# Tea_Cabinet.net
KiCad netlist of a schematic drawn in EAGLE
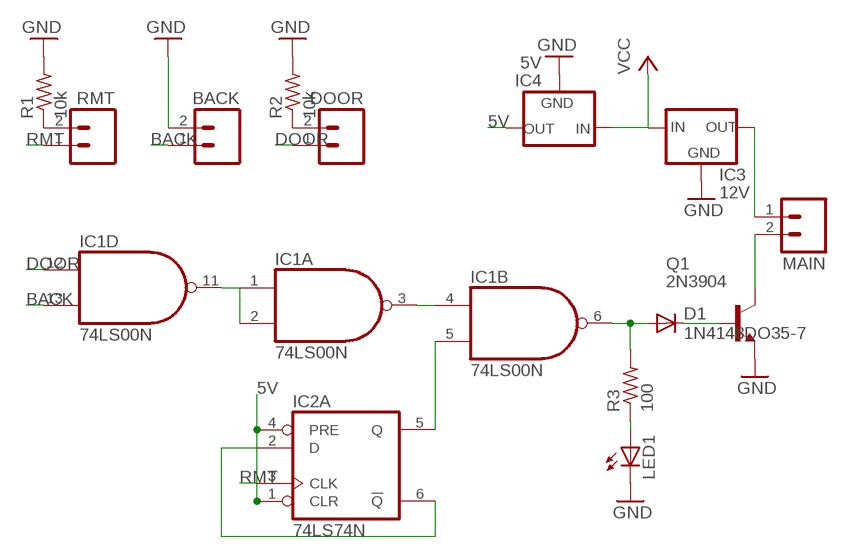
[diagram p0: schematic, sheet 1]

(export (version "E")
  (design (tool "Eeschema 10.0.6"))
  (components
    (comp (ref "BACK")
      (value "M02PTH")
      (footprint "eagle-import:1X02")
      (libsource (lib "eagle-import") (part "M02PTH"))
    )
    (comp (ref "D1")
      (value "1N4148DO35-7")
      (footprint "eagle-import:DO35-7")
      (libsource (lib "eagle-import") (part "1N4148DO35-7"))
    )
    (comp (ref "DOOR")
      (value "M02PTH")
      (footprint "eagle-import:1X02")
      (libsource (lib "eagle-import") (part "M02PTH"))
    )
    (comp (ref "IC1")
      (value "74LS00N")
      (footprint "eagle-import:DIL14")
      (libsource (lib "eagle-import") (part "7400NLS"))
    )
    (comp (ref "IC2")
      (value "74LS74N")
      (footprint "eagle-import:DIL14")
      (libsource (lib "eagle-import") (part "7474NLS"))
    )
    (comp (ref "IC3")
      (value "12V")
      (footprint "eagle-import:78XXS")
      (libsource (lib "eagle-import") (part "78XXS"))
    )
    (comp (ref "IC4")
      (value "5V")
      (footprint "eagle-import:78XXS")
      (libsource (lib "eagle-import") (part "78XXS"))
    )
    (comp (ref "LED1")
      (value "LED5MM")
      (footprint "eagle-import:LED5MM")
      (libsource (lib "eagle-import") (part "LED5MM"))
    )
    (comp (ref "MAIN")
      (value "M02PTH")
      (footprint "eagle-import:1X02")
      (libsource (lib "eagle-import") (part "M02PTH"))
    )
    (comp (ref "Q1")
      (value "2N3904")
      (footprint "eagle-import:TO92")
      (libsource (lib "eagle-import") (part "2N3904"))
    )
    (comp (ref "R1")
      (value "10k")
      (footprint "eagle-import:0204_5")
      (libsource (lib "eagle-import") (part "R-US_0204/5"))
    )
    (comp (ref "R2")
      (value "10k")
      (footprint "eagle-import:0204_5")
      (libsource (lib "eagle-import") (part "R-US_0204/5"))
    )
    (comp (ref "R3")
      (value "100")
      (footprint "eagle-import:0204_5")
      (libsource (lib "eagle-import") (part "R-US_0204/5"))
    )
    (comp (ref "RMT")
      (value "M02PTH")
      (footprint "eagle-import:1X02")
      (libsource (lib "eagle-import") (part "M02PTH"))
    )
  )
  (nets
    (net (code "1") (name "/5V") (class "Default")
      (node (ref "IC2") (pin "1") (pinfunction "CLR_1") (pintype "input"))
      (node (ref "IC2") (pin "4") (pinfunction "PRE_4") (pintype "input"))
      (node (ref "IC4") (pin "OUT") (pinfunction "OUT_OUT") (pintype "passive"))
    )
    (net (code "2") (name "/BACK") (class "Default")
      (node (ref "BACK") (pin "1") (pinfunction "1_1") (pintype "passive"))
      (node (ref "IC1") (pin "13") (pinfunction "I1_13") (pintype "input"))
    )
    (net (code "3") (name "/DOOR") (class "Default")
      (node (ref "DOOR") (pin "1") (pinfunction "1_1") (pintype "passive"))
      (node (ref "IC1") (pin "12") (pinfunction "I0_12") (pintype "input"))
    )
    (net (code "4") (name "/RMT") (class "Default")
      (node (ref "IC2") (pin "3") (pinfunction "CLK_3") (pintype "input"))
      (node (ref "RMT") (pin "1") (pinfunction "1_1") (pintype "passive"))
    )
    (net (code "5") (name "GND") (class "Default")
      (node (ref "BACK") (pin "2") (pinfunction "2_2") (pintype "passive"))
      (node (ref "IC3") (pin "GND") (pinfunction "GND_GND") (pintype "input"))
      (node (ref "IC4") (pin "GND") (pinfunction "GND_GND") (pintype "input"))
      (node (ref "LED1") (pin "K") (pinfunction "C_K") (pintype "passive"))
      (node (ref "Q1") (pin "3") (pinfunction "E_3") (pintype "passive"))
      (node (ref "R1") (pin "2") (pinfunction "2_2") (pintype "passive"))
      (node (ref "R2") (pin "2") (pinfunction "2_2") (pintype "passive"))
    )
    (net (code "6") (name "Net-(DOOR-Pad2)") (class "Default")
      (node (ref "DOOR") (pin "2") (pinfunction "2_2") (pintype "passive"))
      (node (ref "R2") (pin "1") (pinfunction "1_1") (pintype "passive"))
    )
    (net (code "7") (name "Net-(IC1A-I0)") (class "Default")
      (node (ref "IC1") (pin "1") (pinfunction "I0_1") (pintype "input"))
      (node (ref "IC1") (pin "11") (pinfunction "O_11") (pintype "output"))
      (node (ref "IC1") (pin "2") (pinfunction "I1_2") (pintype "input"))
    )
    (net (code "8") (name "Net-(IC1A-O)") (class "Default")
      (node (ref "IC1") (pin "3") (pinfunction "O_3") (pintype "output"))
      (node (ref "IC1") (pin "4") (pinfunction "I0_4") (pintype "input"))
    )
    (net (code "9") (name "Net-(IC1B-I1)") (class "Default")
      (node (ref "IC1") (pin "5") (pinfunction "I1_5") (pintype "input"))
      (node (ref "IC2") (pin "5") (pinfunction "Q_5") (pintype "output"))
    )
    (net (code "10") (name "Net-(IC1B-O)") (class "Default")
      (node (ref "D1") (pin "A") (pinfunction "A_A") (pintype "passive"))
      (node (ref "IC1") (pin "6") (pinfunction "O_6") (pintype "output"))
      (node (ref "R3") (pin "2") (pinfunction "2_2") (pintype "passive"))
    )
    (net (code "11") (name "Net-(IC2A-D)") (class "Default")
      (node (ref "IC2") (pin "2") (pinfunction "D_2") (pintype "input"))
      (node (ref "IC2") (pin "6") (pinfunction "~{Q}_6") (pintype "output"))
    )
    (net (code "12") (name "Net-(IC3-PadOUT)") (class "Default")
      (node (ref "IC3") (pin "OUT") (pinfunction "OUT_OUT") (pintype "passive"))
      (node (ref "MAIN") (pin "1") (pinfunction "1_1") (pintype "passive"))
    )
    (net (code "13") (name "Net-(LED1-PadA)") (class "Default")
      (node (ref "LED1") (pin "A") (pinfunction "A_A") (pintype "passive"))
      (node (ref "R3") (pin "1") (pinfunction "1_1") (pintype "passive"))
    )
    (net (code "14") (name "Net-(Q1-B)") (class "Default")
      (node (ref "D1") (pin "C") (pinfunction "C_C") (pintype "passive"))
      (node (ref "Q1") (pin "2") (pinfunction "B_2") (pintype "passive"))
    )
    (net (code "15") (name "Net-(Q1-C)") (class "Default")
      (node (ref "MAIN") (pin "2") (pinfunction "2_2") (pintype "passive"))
      (node (ref "Q1") (pin "1") (pinfunction "C_1") (pintype "passive"))
    )
    (net (code "16") (name "Net-(R1-Pad1)") (class "Default")
      (node (ref "R1") (pin "1") (pinfunction "1_1") (pintype "passive"))
      (node (ref "RMT") (pin "2") (pinfunction "2_2") (pintype "passive"))
    )
    (net (code "17") (name "VCC") (class "Default")
      (node (ref "IC3") (pin "IN") (pinfunction "IN_IN") (pintype "input"))
      (node (ref "IC4") (pin "IN") (pinfunction "IN_IN") (pintype "input"))
    )
  )
)
